# electronics.net
KiCad netlist of a schematic drawn in EAGLE
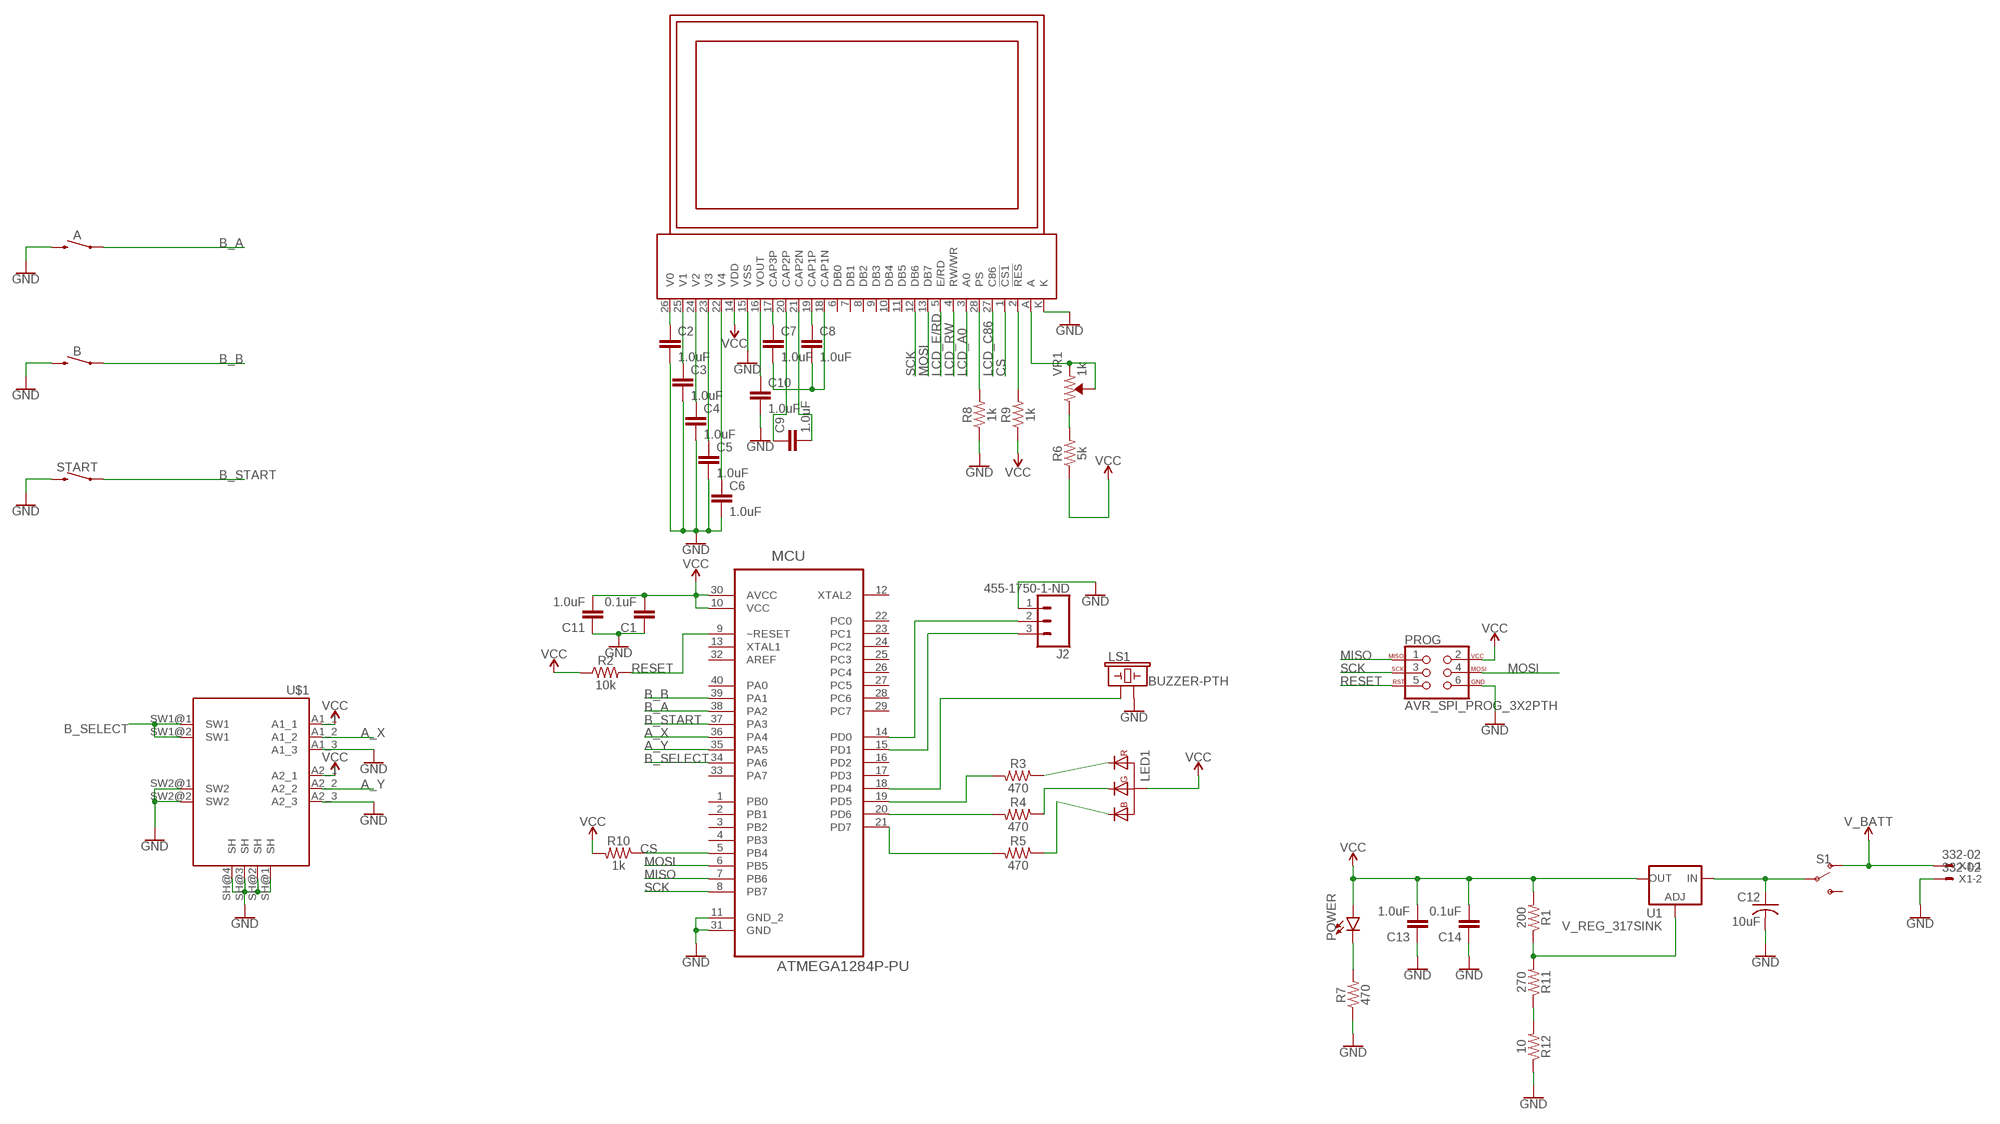
[diagram p0: schematic, sheet 1]

(export (version "E")
  (design (tool "Eeschema 10.0.6"))
  (components
    (comp (ref "A")
      (value "MOMENTARY-SWITCH-SPST-PTH-6.0MM")
      (footprint "eagle-import:TACTILE_SWITCH_PTH_6.0MM")
      (libsource (lib "eagle-import") (part "MOMENTARY-SWITCH-SPST-PTH-6.0MM"))
    )
    (comp (ref "A1")
      (value "LCD")
      (footprint "eagle-import:LCD")
      (libsource (lib "eagle-import") (part "LCD"))
    )
    (comp (ref "B")
      (value "MOMENTARY-SWITCH-SPST-PTH-6.0MM")
      (footprint "eagle-import:TACTILE_SWITCH_PTH_6.0MM")
      (libsource (lib "eagle-import") (part "MOMENTARY-SWITCH-SPST-PTH-6.0MM"))
    )
    (comp (ref "C1")
      (value "0.1uF")
      (footprint "eagle-import:0805")
      (libsource (lib "eagle-import") (part "1.0UF-0805-25V-10%"))
    )
    (comp (ref "C2")
      (value "1.0uF")
      (footprint "eagle-import:0805")
      (libsource (lib "eagle-import") (part "1.0UF-0805-25V-10%"))
    )
    (comp (ref "C3")
      (value "1.0uF")
      (footprint "eagle-import:0805")
      (libsource (lib "eagle-import") (part "1.0UF-0805-25V-10%"))
    )
    (comp (ref "C4")
      (value "1.0uF")
      (footprint "eagle-import:0805")
      (libsource (lib "eagle-import") (part "1.0UF-0805-25V-10%"))
    )
    (comp (ref "C5")
      (value "1.0uF")
      (footprint "eagle-import:0805")
      (libsource (lib "eagle-import") (part "1.0UF-0805-25V-10%"))
    )
    (comp (ref "C6")
      (value "1.0uF")
      (footprint "eagle-import:0805")
      (libsource (lib "eagle-import") (part "1.0UF-0805-25V-10%"))
    )
    (comp (ref "C7")
      (value "1.0uF")
      (footprint "eagle-import:0805")
      (libsource (lib "eagle-import") (part "1.0UF-0805-25V-10%"))
    )
    (comp (ref "C8")
      (value "1.0uF")
      (footprint "eagle-import:0805")
      (libsource (lib "eagle-import") (part "1.0UF-0805-25V-10%"))
    )
    (comp (ref "C9")
      (value "1.0uF")
      (footprint "eagle-import:0805")
      (libsource (lib "eagle-import") (part "1.0UF-0805-25V-10%"))
    )
    (comp (ref "C10")
      (value "1.0uF")
      (footprint "eagle-import:0805")
      (libsource (lib "eagle-import") (part "1.0UF-0805-25V-10%"))
    )
    (comp (ref "C11")
      (value "1.0uF")
      (footprint "eagle-import:0805")
      (libsource (lib "eagle-import") (part "1.0UF-0805-25V-10%"))
    )
    (comp (ref "C12")
      (value "10uF")
      (footprint "eagle-import:C1206")
      (libsource (lib "eagle-import") (part "C-USC1206"))
    )
    (comp (ref "C13")
      (value "1.0uF")
      (footprint "eagle-import:0805")
      (libsource (lib "eagle-import") (part "1.0UF-0805-25V-10%"))
    )
    (comp (ref "C14")
      (value "0.1uF")
      (footprint "eagle-import:0805")
      (libsource (lib "eagle-import") (part "1.0UF-0805-25V-10%"))
    )
    (comp (ref "J2")
      (value "455-1750-1-ND")
      (footprint "eagle-import:1X03")
      (libsource (lib "eagle-import") (part "CONN_03"))
    )
    (comp (ref "LED1")
      (value "RGB_LED")
      (footprint "eagle-import:5MM_LED")
      (libsource (lib "eagle-import") (part "RGB_LED"))
    )
    (comp (ref "LS1")
      (value "BUZZER-PTH")
      (footprint "eagle-import:BUZZER-12MM")
      (libsource (lib "eagle-import") (part "BUZZER-PTH"))
    )
    (comp (ref "MCU")
      (value "ATMEGA1284P-PU")
      (footprint "eagle-import:DIP254P1524X483-40")
      (fields (field (name "MF") "Microchip"))
      (libsource (lib "eagle-import") (part "ATMEGA1284P-PU"))
    )
    (comp (ref "POWER")
      (value "LED5MM")
      (footprint "eagle-import:LED_5MM")
      (libsource (lib "eagle-import") (part "LED5MM"))
    )
    (comp (ref "PROG")
      (value "AVR_SPI_PROG_3X2PTH")
      (footprint "eagle-import:2X3")
      (libsource (lib "eagle-import") (part "AVR_SPI_PROG_3X2PTH"))
    )
    (comp (ref "R1")
      (value "200")
      (footprint "eagle-import:AXIAL-0.3")
      (libsource (lib "eagle-import") (part "1KOHM-HORIZ-1/4W-1%"))
    )
    (comp (ref "R2")
      (value "10k")
      (footprint "eagle-import:0805")
      (libsource (lib "eagle-import") (part "0.3OHM-0805-1/8W-1%"))
    )
    (comp (ref "R3")
      (value "470")
      (footprint "eagle-import:0805")
      (libsource (lib "eagle-import") (part "0.3OHM-0805-1/8W-1%"))
    )
    (comp (ref "R4")
      (value "470")
      (footprint "eagle-import:0805")
      (libsource (lib "eagle-import") (part "0.3OHM-0805-1/8W-1%"))
    )
    (comp (ref "R5")
      (value "470")
      (footprint "eagle-import:0805")
      (libsource (lib "eagle-import") (part "0.3OHM-0805-1/8W-1%"))
    )
    (comp (ref "R6")
      (value "5k")
      (footprint "eagle-import:0805")
      (libsource (lib "eagle-import") (part "0.3OHM-0805-1/8W-1%"))
    )
    (comp (ref "R7")
      (value "470")
      (footprint "eagle-import:0805")
      (libsource (lib "eagle-import") (part "0.3OHM-0805-1/8W-1%"))
    )
    (comp (ref "R8")
      (value "1k")
      (footprint "eagle-import:0805")
      (libsource (lib "eagle-import") (part "0.3OHM-0805-1/8W-1%"))
    )
    (comp (ref "R9")
      (value "1k")
      (footprint "eagle-import:0805")
      (libsource (lib "eagle-import") (part "0.3OHM-0805-1/8W-1%"))
    )
    (comp (ref "R10")
      (value "1k")
      (footprint "eagle-import:0805")
      (libsource (lib "eagle-import") (part "0.3OHM-0805-1/8W-1%"))
    )
    (comp (ref "R11")
      (value "270")
      (footprint "eagle-import:AXIAL-0.3")
      (libsource (lib "eagle-import") (part "1KOHM-HORIZ-1/4W-1%"))
    )
    (comp (ref "R12")
      (value "10")
      (footprint "eagle-import:AXIAL-0.3")
      (libsource (lib "eagle-import") (part "1KOHM-HORIZ-1/4W-1%"))
    )
    (comp (ref "S1")
      (value "SWITCH-SPDT-PTH-11.6X4.0MM")
      (footprint "eagle-import:SWITCH_SPDT_PTH_11.6X4.0MM")
      (libsource (lib "eagle-import") (part "SWITCH-SPDT-PTH-11.6X4.0MM"))
    )
    (comp (ref "START")
      (value "MOMENTARY-SWITCH-SPST-PTH-6.0MM")
      (footprint "eagle-import:TACTILE_SWITCH_PTH_6.0MM")
      (libsource (lib "eagle-import") (part "MOMENTARY-SWITCH-SPST-PTH-6.0MM"))
    )
    (comp (ref "U$1")
      (value "JOYSTICK")
      (footprint "eagle-import:JOY")
      (libsource (lib "eagle-import") (part "JOYSTICK"))
    )
    (comp (ref "U1")
      (value "V_REG_317SINK")
      (footprint "eagle-import:TO220-ADJ")
      (libsource (lib "eagle-import") (part "V_REG_317SINK"))
    )
    (comp (ref "VR1")
      (value "1k")
      (footprint "eagle-import:TRIMPOT-PTH-3386U")
      (libsource (lib "eagle-import") (part "TRIMPOT-PTH-10MM-KNOB-1/2W-10%"))
    )
    (comp (ref "X1")
      (value "332-02")
      (footprint "eagle-import:332-02")
      (libsource (lib "eagle-import") (part "332-02"))
    )
  )
  (nets
    (net (code "1") (name "/A_X") (class "Default")
      (node (ref "MCU") (pin "36") (pinfunction "PA4_36") (pintype "bidirectional"))
      (node (ref "U$1") (pin "A1_2") (pinfunction "A1_2_A1_2") (pintype "bidirectional"))
    )
    (net (code "2") (name "/A_Y") (class "Default")
      (node (ref "MCU") (pin "35") (pinfunction "PA5_35") (pintype "bidirectional"))
      (node (ref "U$1") (pin "A2_2") (pinfunction "A2_2_A2_2") (pintype "bidirectional"))
    )
    (net (code "3") (name "/B_A") (class "Default")
      (node (ref "A") (pin "1") (pinfunction "1_1") (pintype "passive"))
      (node (ref "MCU") (pin "38") (pinfunction "PA2_38") (pintype "bidirectional"))
    )
    (net (code "4") (name "/B_B") (class "Default")
      (node (ref "B") (pin "1") (pinfunction "1_1") (pintype "passive"))
      (node (ref "MCU") (pin "39") (pinfunction "PA1_39") (pintype "bidirectional"))
    )
    (net (code "5") (name "/B_SELECT") (class "Default")
      (node (ref "MCU") (pin "34") (pinfunction "PA6_34") (pintype "bidirectional"))
      (node (ref "U$1") (pin "SW1@1") (pinfunction "SW1_SW1@1") (pintype "bidirectional"))
      (node (ref "U$1") (pin "SW1@2") (pinfunction "SW1_SW1@2") (pintype "bidirectional"))
    )
    (net (code "6") (name "/B_START") (class "Default")
      (node (ref "MCU") (pin "37") (pinfunction "PA3_37") (pintype "bidirectional"))
      (node (ref "START") (pin "1") (pinfunction "1_1") (pintype "passive"))
    )
    (net (code "7") (name "/CS") (class "Default")
      (node (ref "A1") (pin "1") (pinfunction "~{CS1}_1") (pintype "bidirectional"))
      (node (ref "MCU") (pin "5") (pinfunction "PB4_5") (pintype "bidirectional"))
      (node (ref "R10") (pin "1") (pinfunction "1_1") (pintype "passive"))
    )
    (net (code "8") (name "/LCD_A0") (class "Default")
      (node (ref "A1") (pin "3") (pinfunction "A0_3") (pintype "bidirectional"))
    )
    (net (code "9") (name "/LCD_C86") (class "Default")
      (node (ref "A1") (pin "27") (pinfunction "C86_27") (pintype "bidirectional"))
    )
    (net (code "10") (name "/LCD_E{slash}RD") (class "Default")
      (node (ref "A1") (pin "5") (pinfunction "E/RD_5") (pintype "bidirectional"))
    )
    (net (code "11") (name "/LCD_RW") (class "Default")
      (node (ref "A1") (pin "4") (pinfunction "RW/WR_4") (pintype "bidirectional"))
    )
    (net (code "12") (name "/MISO") (class "Default")
      (node (ref "MCU") (pin "7") (pinfunction "PB6_7") (pintype "bidirectional"))
      (node (ref "PROG") (pin "1") (pinfunction "1_1") (pintype "passive"))
    )
    (net (code "13") (name "/MOSI") (class "Default")
      (node (ref "A1") (pin "13") (pinfunction "DB7_13") (pintype "bidirectional"))
      (node (ref "MCU") (pin "6") (pinfunction "PB5_6") (pintype "bidirectional"))
      (node (ref "PROG") (pin "4") (pinfunction "4_4") (pintype "passive"))
    )
    (net (code "14") (name "/RESET") (class "Default")
      (node (ref "MCU") (pin "9") (pinfunction "~{RESET}_9") (pintype "input"))
      (node (ref "PROG") (pin "5") (pinfunction "5_5") (pintype "passive"))
      (node (ref "R2") (pin "2") (pinfunction "2_2") (pintype "passive"))
    )
    (net (code "15") (name "/SCK") (class "Default")
      (node (ref "A1") (pin "12") (pinfunction "DB6_12") (pintype "bidirectional"))
      (node (ref "MCU") (pin "8") (pinfunction "PB7_8") (pintype "bidirectional"))
      (node (ref "PROG") (pin "3") (pinfunction "3_3") (pintype "passive"))
    )
    (net (code "16") (name "GND") (class "Default")
      (node (ref "A") (pin "3") (pinfunction "2_3") (pintype "passive"))
      (node (ref "A1") (pin "15") (pinfunction "VSS_15") (pintype "bidirectional"))
      (node (ref "A1") (pin "K") (pinfunction "K_K") (pintype "bidirectional"))
      (node (ref "B") (pin "3") (pinfunction "2_3") (pintype "passive"))
      (node (ref "C1") (pin "1") (pinfunction "1_1") (pintype "passive"))
      (node (ref "C10") (pin "2") (pinfunction "2_2") (pintype "passive"))
      (node (ref "C11") (pin "1") (pinfunction "1_1") (pintype "passive"))
      (node (ref "C12") (pin "2") (pinfunction "2_2") (pintype "passive"))
      (node (ref "C13") (pin "1") (pinfunction "1_1") (pintype "passive"))
      (node (ref "C14") (pin "1") (pinfunction "1_1") (pintype "passive"))
      (node (ref "C2") (pin "2") (pinfunction "2_2") (pintype "passive"))
      (node (ref "C3") (pin "2") (pinfunction "2_2") (pintype "passive"))
      (node (ref "C4") (pin "2") (pinfunction "2_2") (pintype "passive"))
      (node (ref "C5") (pin "2") (pinfunction "2_2") (pintype "passive"))
      (node (ref "C6") (pin "2") (pinfunction "2_2") (pintype "passive"))
      (node (ref "J2") (pin "1") (pinfunction "1_1") (pintype "passive"))
      (node (ref "LS1") (pin "-") (pinfunction "2_-") (pintype "passive"))
      (node (ref "MCU") (pin "11") (pinfunction "GND_2_11") (pintype "passive"))
      (node (ref "MCU") (pin "31") (pinfunction "GND_31") (pintype "passive"))
      (node (ref "PROG") (pin "6") (pinfunction "6_6") (pintype "passive"))
      (node (ref "R12") (pin "P$1") (pinfunction "1_P$1") (pintype "passive"))
      (node (ref "R7") (pin "1") (pinfunction "1_1") (pintype "passive"))
      (node (ref "R8") (pin "1") (pinfunction "1_1") (pintype "passive"))
      (node (ref "START") (pin "3") (pinfunction "2_3") (pintype "passive"))
      (node (ref "U$1") (pin "A1_3") (pinfunction "A1_3_A1_3") (pintype "bidirectional"))
      (node (ref "U$1") (pin "A2_3") (pinfunction "A2_3_A2_3") (pintype "bidirectional"))
      (node (ref "U$1") (pin "SH@1") (pinfunction "SH_SH@1") (pintype "bidirectional"))
      (node (ref "U$1") (pin "SH@2") (pinfunction "SH_SH@2") (pintype "bidirectional"))
      (node (ref "U$1") (pin "SH@3") (pinfunction "SH_SH@3") (pintype "bidirectional"))
      (node (ref "U$1") (pin "SH@4") (pinfunction "SH_SH@4") (pintype "bidirectional"))
      (node (ref "U$1") (pin "SW2@1") (pinfunction "SW2_SW2@1") (pintype "bidirectional"))
      (node (ref "U$1") (pin "SW2@2") (pinfunction "SW2_SW2@2") (pintype "bidirectional"))
      (node (ref "X1") (pin "2") (pinfunction "S_2") (pintype "passive"))
    )
    (net (code "17") (name "Net-(A1-CAP1N)") (class "Default")
      (node (ref "A1") (pin "18") (pinfunction "CAP1N_18") (pintype "bidirectional"))
      (node (ref "C7") (pin "2") (pinfunction "2_2") (pintype "passive"))
      (node (ref "C8") (pin "2") (pinfunction "2_2") (pintype "passive"))
    )
    (net (code "18") (name "Net-(A1-CAP1P)") (class "Default")
      (node (ref "A1") (pin "19") (pinfunction "CAP1P_19") (pintype "bidirectional"))
      (node (ref "C8") (pin "1") (pinfunction "1_1") (pintype "passive"))
    )
    (net (code "19") (name "Net-(A1-CAP2N)") (class "Default")
      (node (ref "A1") (pin "21") (pinfunction "CAP2N_21") (pintype "bidirectional"))
      (node (ref "C9") (pin "2") (pinfunction "2_2") (pintype "passive"))
    )
    (net (code "20") (name "Net-(A1-CAP2P)") (class "Default")
      (node (ref "A1") (pin "20") (pinfunction "CAP2P_20") (pintype "bidirectional"))
      (node (ref "C9") (pin "1") (pinfunction "1_1") (pintype "passive"))
    )
    (net (code "21") (name "Net-(A1-CAP3P)") (class "Default")
      (node (ref "A1") (pin "17") (pinfunction "CAP3P_17") (pintype "bidirectional"))
      (node (ref "C7") (pin "1") (pinfunction "1_1") (pintype "passive"))
    )
    (net (code "22") (name "Net-(A1-PS)") (class "Default")
      (node (ref "A1") (pin "28") (pinfunction "PS_28") (pintype "bidirectional"))
      (node (ref "R8") (pin "2") (pinfunction "2_2") (pintype "passive"))
    )
    (net (code "23") (name "Net-(A1-V0)") (class "Default")
      (node (ref "A1") (pin "26") (pinfunction "V0_26") (pintype "bidirectional"))
      (node (ref "C2") (pin "1") (pinfunction "1_1") (pintype "passive"))
    )
    (net (code "24") (name "Net-(A1-V1)") (class "Default")
      (node (ref "A1") (pin "25") (pinfunction "V1_25") (pintype "bidirectional"))
      (node (ref "C3") (pin "1") (pinfunction "1_1") (pintype "passive"))
    )
    (net (code "25") (name "Net-(A1-V2)") (class "Default")
      (node (ref "A1") (pin "24") (pinfunction "V2_24") (pintype "bidirectional"))
      (node (ref "C4") (pin "1") (pinfunction "1_1") (pintype "passive"))
    )
    (net (code "26") (name "Net-(A1-V3)") (class "Default")
      (node (ref "A1") (pin "23") (pinfunction "V3_23") (pintype "bidirectional"))
      (node (ref "C5") (pin "1") (pinfunction "1_1") (pintype "passive"))
    )
    (net (code "27") (name "Net-(A1-V4)") (class "Default")
      (node (ref "A1") (pin "22") (pinfunction "V4_22") (pintype "bidirectional"))
      (node (ref "C6") (pin "1") (pinfunction "1_1") (pintype "passive"))
    )
    (net (code "28") (name "Net-(A1-VOUT)") (class "Default")
      (node (ref "A1") (pin "16") (pinfunction "VOUT_16") (pintype "bidirectional"))
      (node (ref "C10") (pin "1") (pinfunction "1_1") (pintype "passive"))
    )
    (net (code "29") (name "Net-(A1-~{RES})") (class "Default")
      (node (ref "A1") (pin "2") (pinfunction "~{RES}_2") (pintype "bidirectional"))
      (node (ref "R9") (pin "2") (pinfunction "2_2") (pintype "passive"))
    )
    (net (code "30") (name "Net-(LED1-PadB)") (class "Default")
      (node (ref "LED1") (pin "B") (pinfunction "B_B") (pintype "bidirectional"))
      (node (ref "R5") (pin "1") (pinfunction "1_1") (pintype "passive"))
    )
    (net (code "31") (name "Net-(LED1-PadG)") (class "Default")
      (node (ref "LED1") (pin "G") (pinfunction "G_G") (pintype "bidirectional"))
      (node (ref "R4") (pin "1") (pinfunction "1_1") (pintype "passive"))
    )
    (net (code "32") (name "Net-(LED1-PadR)") (class "Default")
      (node (ref "LED1") (pin "R") (pinfunction "R_R") (pintype "bidirectional"))
      (node (ref "R3") (pin "1") (pinfunction "1_1") (pintype "passive"))
    )
    (net (code "33") (name "Net-(LS1-1)") (class "Default")
      (node (ref "LS1") (pin "+") (pinfunction "1_+") (pintype "passive"))
      (node (ref "MCU") (pin "18") (pinfunction "PD4_18") (pintype "bidirectional"))
    )
    (net (code "34") (name "Net-(MCU-PD0)") (class "Default")
      (node (ref "J2") (pin "2") (pinfunction "2_2") (pintype "passive"))
      (node (ref "MCU") (pin "14") (pinfunction "PD0_14") (pintype "bidirectional"))
    )
    (net (code "35") (name "Net-(MCU-PD1)") (class "Default")
      (node (ref "J2") (pin "3") (pinfunction "3_3") (pintype "passive"))
      (node (ref "MCU") (pin "15") (pinfunction "PD1_15") (pintype "bidirectional"))
    )
    (net (code "36") (name "Net-(MCU-PD5)") (class "Default")
      (node (ref "MCU") (pin "19") (pinfunction "PD5_19") (pintype "bidirectional"))
      (node (ref "R3") (pin "2") (pinfunction "2_2") (pintype "passive"))
    )
    (net (code "37") (name "Net-(MCU-PD6)") (class "Default")
      (node (ref "MCU") (pin "20") (pinfunction "PD6_20") (pintype "bidirectional"))
      (node (ref "R4") (pin "2") (pinfunction "2_2") (pintype "passive"))
    )
    (net (code "38") (name "Net-(MCU-PD7)") (class "Default")
      (node (ref "MCU") (pin "21") (pinfunction "PD7_21") (pintype "bidirectional"))
      (node (ref "R5") (pin "2") (pinfunction "2_2") (pintype "passive"))
    )
    (net (code "39") (name "Net-(POWER-C)") (class "Default")
      (node (ref "POWER") (pin "K") (pinfunction "C_K") (pintype "passive"))
      (node (ref "R7") (pin "2") (pinfunction "2_2") (pintype "passive"))
    )
    (net (code "40") (name "Net-(R1-1)") (class "Default")
      (node (ref "R1") (pin "P$1") (pinfunction "1_P$1") (pintype "passive"))
      (node (ref "R11") (pin "P$2") (pinfunction "2_P$2") (pintype "passive"))
      (node (ref "U1") (pin "ADJ") (pinfunction "ADJ_ADJ") (pintype "input"))
    )
    (net (code "41") (name "Net-(R11-1)") (class "Default")
      (node (ref "R11") (pin "P$1") (pinfunction "1_P$1") (pintype "passive"))
      (node (ref "R12") (pin "P$2") (pinfunction "2_P$2") (pintype "passive"))
    )
    (net (code "42") (name "Net-(S1-P)") (class "Default")
      (node (ref "C12") (pin "1") (pinfunction "1_1") (pintype "passive"))
      (node (ref "S1") (pin "2") (pinfunction "P_2") (pintype "passive"))
      (node (ref "U1") (pin "IN") (pinfunction "IN_IN") (pintype "input"))
    )
    (net (code "43") (name "Net-(VR1-CCW)") (class "Default")
      (node (ref "A1") (pin "A") (pinfunction "A_A") (pintype "bidirectional"))
      (node (ref "VR1") (pin "1") (pinfunction "CCW_1") (pintype "passive"))
      (node (ref "VR1") (pin "2") (pinfunction "WIPER_2") (pintype "passive"))
    )
    (net (code "44") (name "Net-(VR1-CW)") (class "Default")
      (node (ref "R6") (pin "2") (pinfunction "2_2") (pintype "passive"))
      (node (ref "VR1") (pin "3") (pinfunction "CW_3") (pintype "passive"))
    )
    (net (code "45") (name "VCC") (class "Default")
      (node (ref "A1") (pin "14") (pinfunction "VDD_14") (pintype "bidirectional"))
      (node (ref "C1") (pin "2") (pinfunction "2_2") (pintype "passive"))
      (node (ref "C11") (pin "2") (pinfunction "2_2") (pintype "passive"))
      (node (ref "C13") (pin "2") (pinfunction "2_2") (pintype "passive"))
      (node (ref "C14") (pin "2") (pinfunction "2_2") (pintype "passive"))
      (node (ref "LED1") (pin "C") (pinfunction "A_C") (pintype "bidirectional"))
      (node (ref "MCU") (pin "10") (pinfunction "VCC_10") (pintype "power_in"))
      (node (ref "MCU") (pin "30") (pinfunction "AVCC_30") (pintype "power_in"))
      (node (ref "POWER") (pin "A") (pinfunction "A_A") (pintype "passive"))
      (node (ref "PROG") (pin "2") (pinfunction "2_2") (pintype "passive"))
      (node (ref "R1") (pin "P$2") (pinfunction "2_P$2") (pintype "passive"))
      (node (ref "R10") (pin "2") (pinfunction "2_2") (pintype "passive"))
      (node (ref "R2") (pin "1") (pinfunction "1_1") (pintype "passive"))
      (node (ref "R6") (pin "1") (pinfunction "1_1") (pintype "passive"))
      (node (ref "R9") (pin "1") (pinfunction "1_1") (pintype "passive"))
      (node (ref "U$1") (pin "A1_1") (pinfunction "A1_1_A1_1") (pintype "bidirectional"))
      (node (ref "U$1") (pin "A2_1") (pinfunction "A2_1_A2_1") (pintype "bidirectional"))
      (node (ref "U1") (pin "OUT") (pinfunction "OUT_OUT") (pintype "output"))
    )
    (net (code "46") (name "V_BATT") (class "Default")
      (node (ref "S1") (pin "1") (pinfunction "O_1") (pintype "passive"))
      (node (ref "X1") (pin "1") (pinfunction "S_1") (pintype "passive"))
    )
    (net (code "47") (name "unconnected-(A1-DB0-Pad6)") (class "Default")
      (node (ref "A1") (pin "6") (pinfunction "DB0_6") (pintype "bidirectional"))
    )
    (net (code "48") (name "unconnected-(A1-DB1-Pad7)") (class "Default")
      (node (ref "A1") (pin "7") (pinfunction "DB1_7") (pintype "bidirectional"))
    )
    (net (code "49") (name "unconnected-(A1-DB2-Pad8)") (class "Default")
      (node (ref "A1") (pin "8") (pinfunction "DB2_8") (pintype "bidirectional"))
    )
    (net (code "50") (name "unconnected-(A1-DB3-Pad9)") (class "Default")
      (node (ref "A1") (pin "9") (pinfunction "DB3_9") (pintype "bidirectional"))
    )
    (net (code "51") (name "unconnected-(A1-DB4-Pad10)") (class "Default")
      (node (ref "A1") (pin "10") (pinfunction "DB4_10") (pintype "bidirectional"))
    )
    (net (code "52") (name "unconnected-(A1-DB5-Pad11)") (class "Default")
      (node (ref "A1") (pin "11") (pinfunction "DB5_11") (pintype "bidirectional"))
    )
    (net (code "53") (name "unconnected-(MCU-AREF-Pad32)") (class "Default")
      (node (ref "MCU") (pin "32") (pinfunction "AREF_32") (pintype "input"))
    )
    (net (code "54") (name "unconnected-(MCU-PA0-Pad40)") (class "Default")
      (node (ref "MCU") (pin "40") (pinfunction "PA0_40") (pintype "bidirectional"))
    )
    (net (code "55") (name "unconnected-(MCU-PA7-Pad33)") (class "Default")
      (node (ref "MCU") (pin "33") (pinfunction "PA7_33") (pintype "bidirectional"))
    )
    (net (code "56") (name "unconnected-(MCU-PB0-Pad1)") (class "Default")
      (node (ref "MCU") (pin "1") (pinfunction "PB0_1") (pintype "bidirectional"))
    )
    (net (code "57") (name "unconnected-(MCU-PB1-Pad2)") (class "Default")
      (node (ref "MCU") (pin "2") (pinfunction "PB1_2") (pintype "bidirectional"))
    )
    (net (code "58") (name "unconnected-(MCU-PB2-Pad3)") (class "Default")
      (node (ref "MCU") (pin "3") (pinfunction "PB2_3") (pintype "bidirectional"))
    )
    (net (code "59") (name "unconnected-(MCU-PB3-Pad4)") (class "Default")
      (node (ref "MCU") (pin "4") (pinfunction "PB3_4") (pintype "bidirectional"))
    )
    (net (code "60") (name "unconnected-(MCU-PC0-Pad22)") (class "Default")
      (node (ref "MCU") (pin "22") (pinfunction "PC0_22") (pintype "bidirectional"))
    )
    (net (code "61") (name "unconnected-(MCU-PC1-Pad23)") (class "Default")
      (node (ref "MCU") (pin "23") (pinfunction "PC1_23") (pintype "bidirectional"))
    )
    (net (code "62") (name "unconnected-(MCU-PC2-Pad24)") (class "Default")
      (node (ref "MCU") (pin "24") (pinfunction "PC2_24") (pintype "bidirectional"))
    )
    (net (code "63") (name "unconnected-(MCU-PC3-Pad25)") (class "Default")
      (node (ref "MCU") (pin "25") (pinfunction "PC3_25") (pintype "bidirectional"))
    )
    (net (code "64") (name "unconnected-(MCU-PC4-Pad26)") (class "Default")
      (node (ref "MCU") (pin "26") (pinfunction "PC4_26") (pintype "bidirectional"))
    )
    (net (code "65") (name "unconnected-(MCU-PC5-Pad27)") (class "Default")
      (node (ref "MCU") (pin "27") (pinfunction "PC5_27") (pintype "bidirectional"))
    )
    (net (code "66") (name "unconnected-(MCU-PC6-Pad28)") (class "Default")
      (node (ref "MCU") (pin "28") (pinfunction "PC6_28") (pintype "bidirectional"))
    )
    (net (code "67") (name "unconnected-(MCU-PC7-Pad29)") (class "Default")
      (node (ref "MCU") (pin "29") (pinfunction "PC7_29") (pintype "bidirectional"))
    )
    (net (code "68") (name "unconnected-(MCU-PD2-Pad16)") (class "Default")
      (node (ref "MCU") (pin "16") (pinfunction "PD2_16") (pintype "bidirectional"))
    )
    (net (code "69") (name "unconnected-(MCU-PD3-Pad17)") (class "Default")
      (node (ref "MCU") (pin "17") (pinfunction "PD3_17") (pintype "bidirectional"))
    )
    (net (code "70") (name "unconnected-(MCU-XTAL1-Pad13)") (class "Default")
      (node (ref "MCU") (pin "13") (pinfunction "XTAL1_13") (pintype "input"))
    )
    (net (code "71") (name "unconnected-(MCU-XTAL2-Pad12)") (class "Default")
      (node (ref "MCU") (pin "12") (pinfunction "XTAL2_12") (pintype "output"))
    )
    (net (code "72") (name "unconnected-(S1-S-Pad3)") (class "Default")
      (node (ref "S1") (pin "3") (pinfunction "S_3") (pintype "passive"))
    )
  )
)
